# OptoEndSwitch.net
KiCad netlist of a schematic drawn in EAGLE
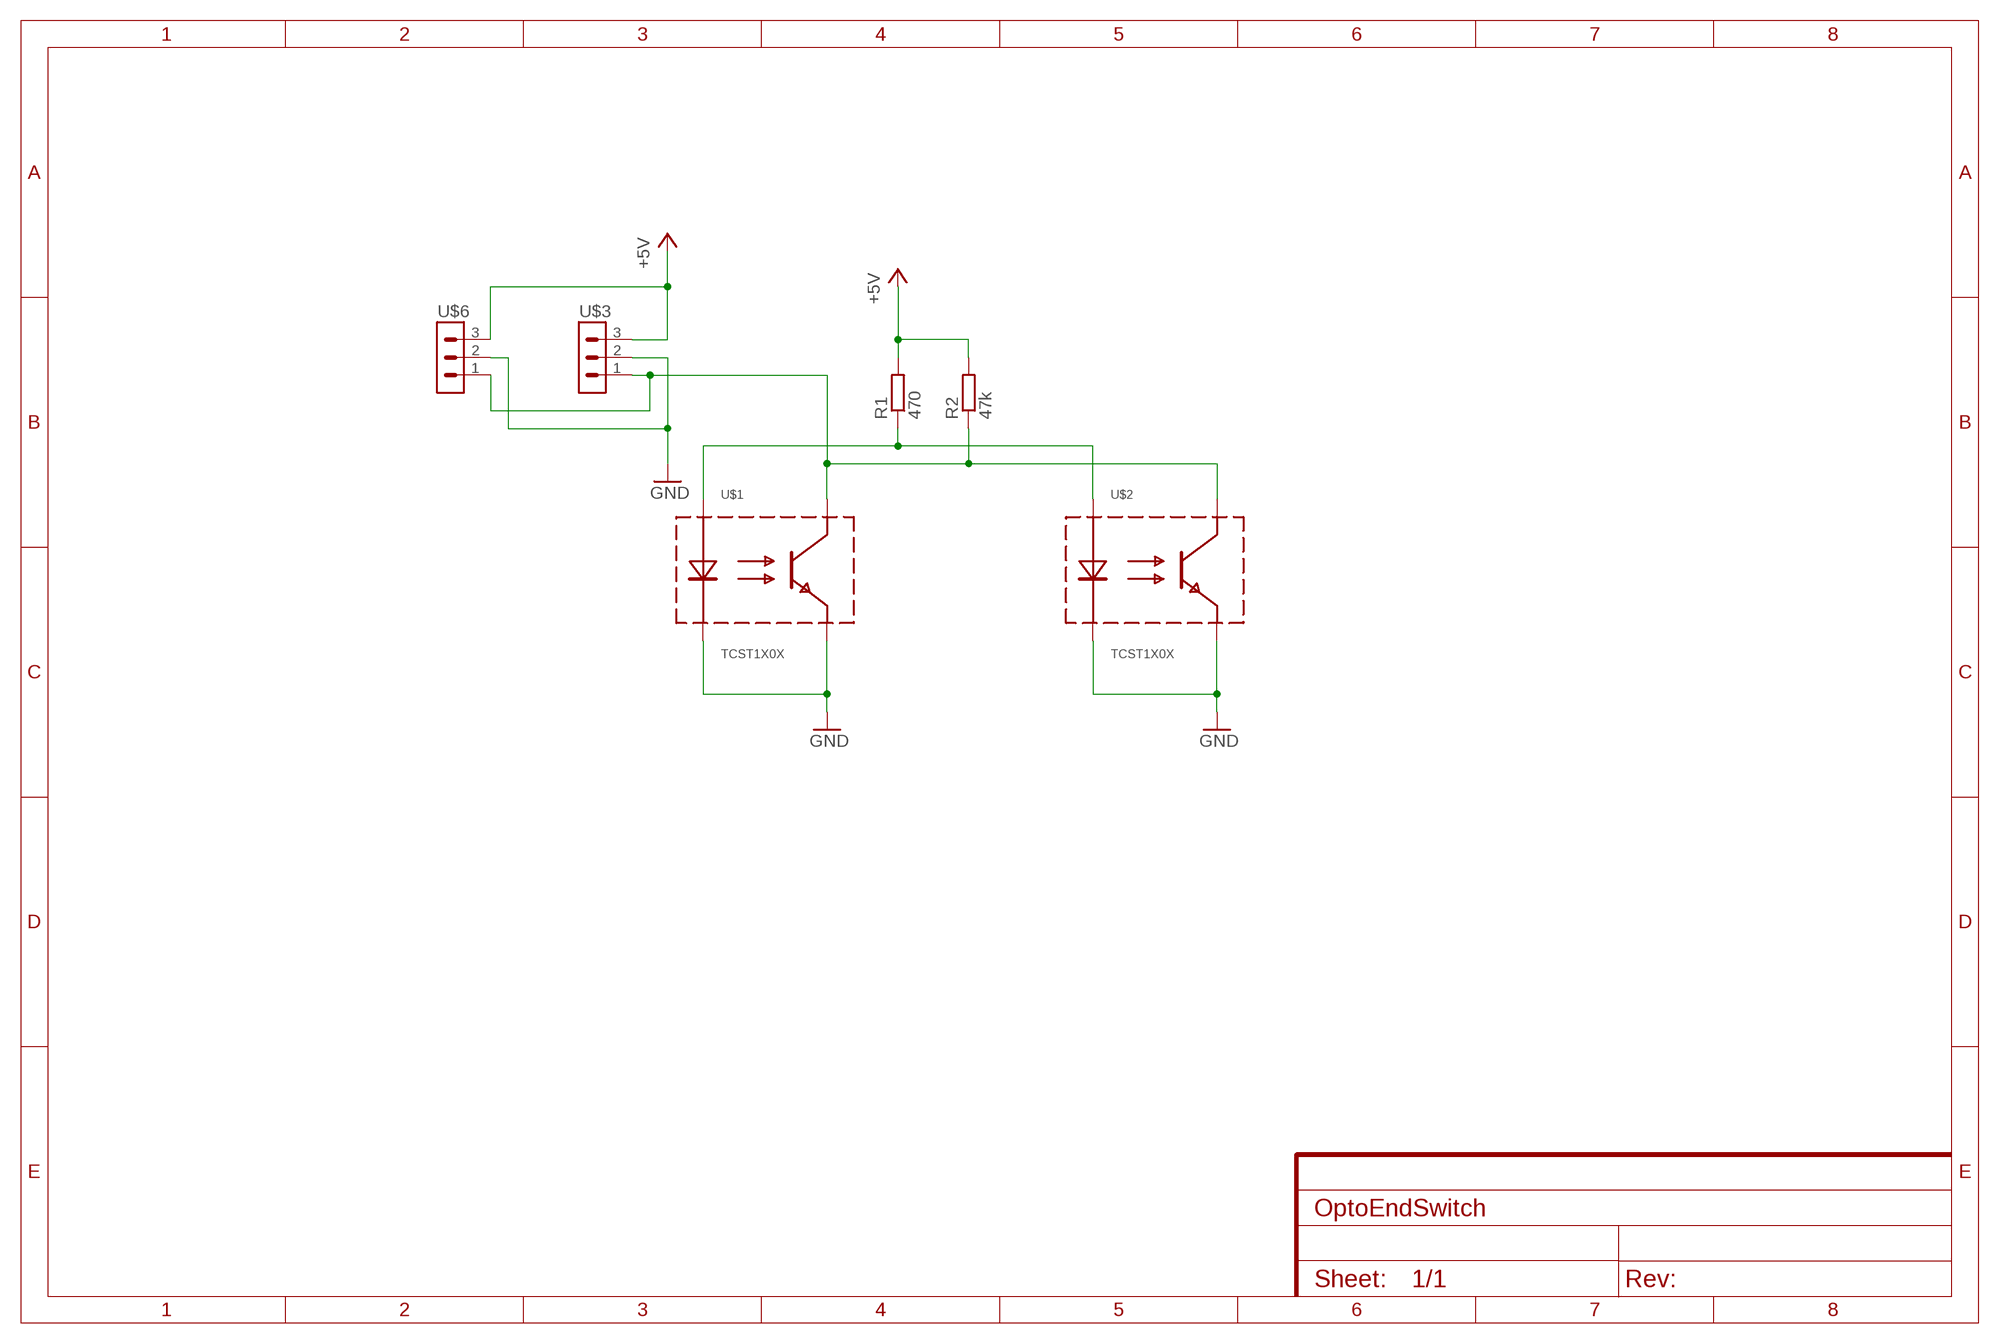
[diagram p0: schematic, sheet 1]

(export (version "E")
  (design (tool "Eeschema 10.0.6"))
  (components
    (comp (ref "R1")
      (value "470")
      (footprint "eagle-import:0207_10")
      (libsource (lib "eagle-import") (part "R-EU_0207/10"))
    )
    (comp (ref "R2")
      (value "47k")
      (footprint "eagle-import:0207_10")
      (libsource (lib "eagle-import") (part "R-EU_0207/10"))
    )
    (comp (ref "U$1")
      (value "TCST1X0X")
      (footprint "eagle-import:TCST1X0X")
      (libsource (lib "eagle-import") (part "TCST1X0X"))
    )
    (comp (ref "U$2")
      (value "TCST1X0X")
      (footprint "eagle-import:TCST1X0X")
      (libsource (lib "eagle-import") (part "TCST1X0X"))
    )
    (comp (ref "U$3")
      (value "JST-3PSIDE-SHORT")
      (footprint "eagle-import:XH-A-1-SIDE-3P")
      (libsource (lib "eagle-import") (part "JST-3PSIDE-SHORT"))
    )
    (comp (ref "U$6")
      (value "JST-3PSIDE-SHORT")
      (footprint "eagle-import:XH-A-1-SIDE-3P")
      (libsource (lib "eagle-import") (part "JST-3PSIDE-SHORT"))
    )
  )
  (nets
    (net (code "1") (name "+5V") (class "Default")
      (node (ref "R1") (pin "2") (pinfunction "2_2") (pintype "passive"))
      (node (ref "R2") (pin "2") (pinfunction "2_2") (pintype "passive"))
      (node (ref "U$3") (pin "3") (pinfunction "3_3") (pintype "bidirectional"))
      (node (ref "U$6") (pin "3") (pinfunction "3_3") (pintype "bidirectional"))
    )
    (net (code "2") (name "GND") (class "Default")
      (node (ref "U$1") (pin "D") (pinfunction "D_D") (pintype "bidirectional"))
      (node (ref "U$1") (pin "E") (pinfunction "E_E") (pintype "bidirectional"))
      (node (ref "U$2") (pin "D") (pinfunction "D_D") (pintype "bidirectional"))
      (node (ref "U$2") (pin "E") (pinfunction "E_E") (pintype "bidirectional"))
      (node (ref "U$3") (pin "2") (pinfunction "2_2") (pintype "bidirectional"))
      (node (ref "U$6") (pin "2") (pinfunction "2_2") (pintype "bidirectional"))
    )
    (net (code "3") (name "Net-(R1-Pad1)") (class "Default")
      (node (ref "R1") (pin "1") (pinfunction "1_1") (pintype "passive"))
      (node (ref "U$1") (pin "E+") (pinfunction "E+_E+") (pintype "bidirectional"))
      (node (ref "U$2") (pin "E+") (pinfunction "E+_E+") (pintype "bidirectional"))
    )
    (net (code "4") (name "Net-(R2-Pad1)") (class "Default")
      (node (ref "R2") (pin "1") (pinfunction "1_1") (pintype "passive"))
      (node (ref "U$1") (pin "D+") (pinfunction "D+_D+") (pintype "bidirectional"))
      (node (ref "U$2") (pin "D+") (pinfunction "D+_D+") (pintype "bidirectional"))
      (node (ref "U$3") (pin "1") (pinfunction "1_1") (pintype "bidirectional"))
      (node (ref "U$6") (pin "1") (pinfunction "1_1") (pintype "bidirectional"))
    )
  )
)
